# SCH_UWB_2026-08-28.net
KiCad netlist of a schematic drawn in EasyEDA
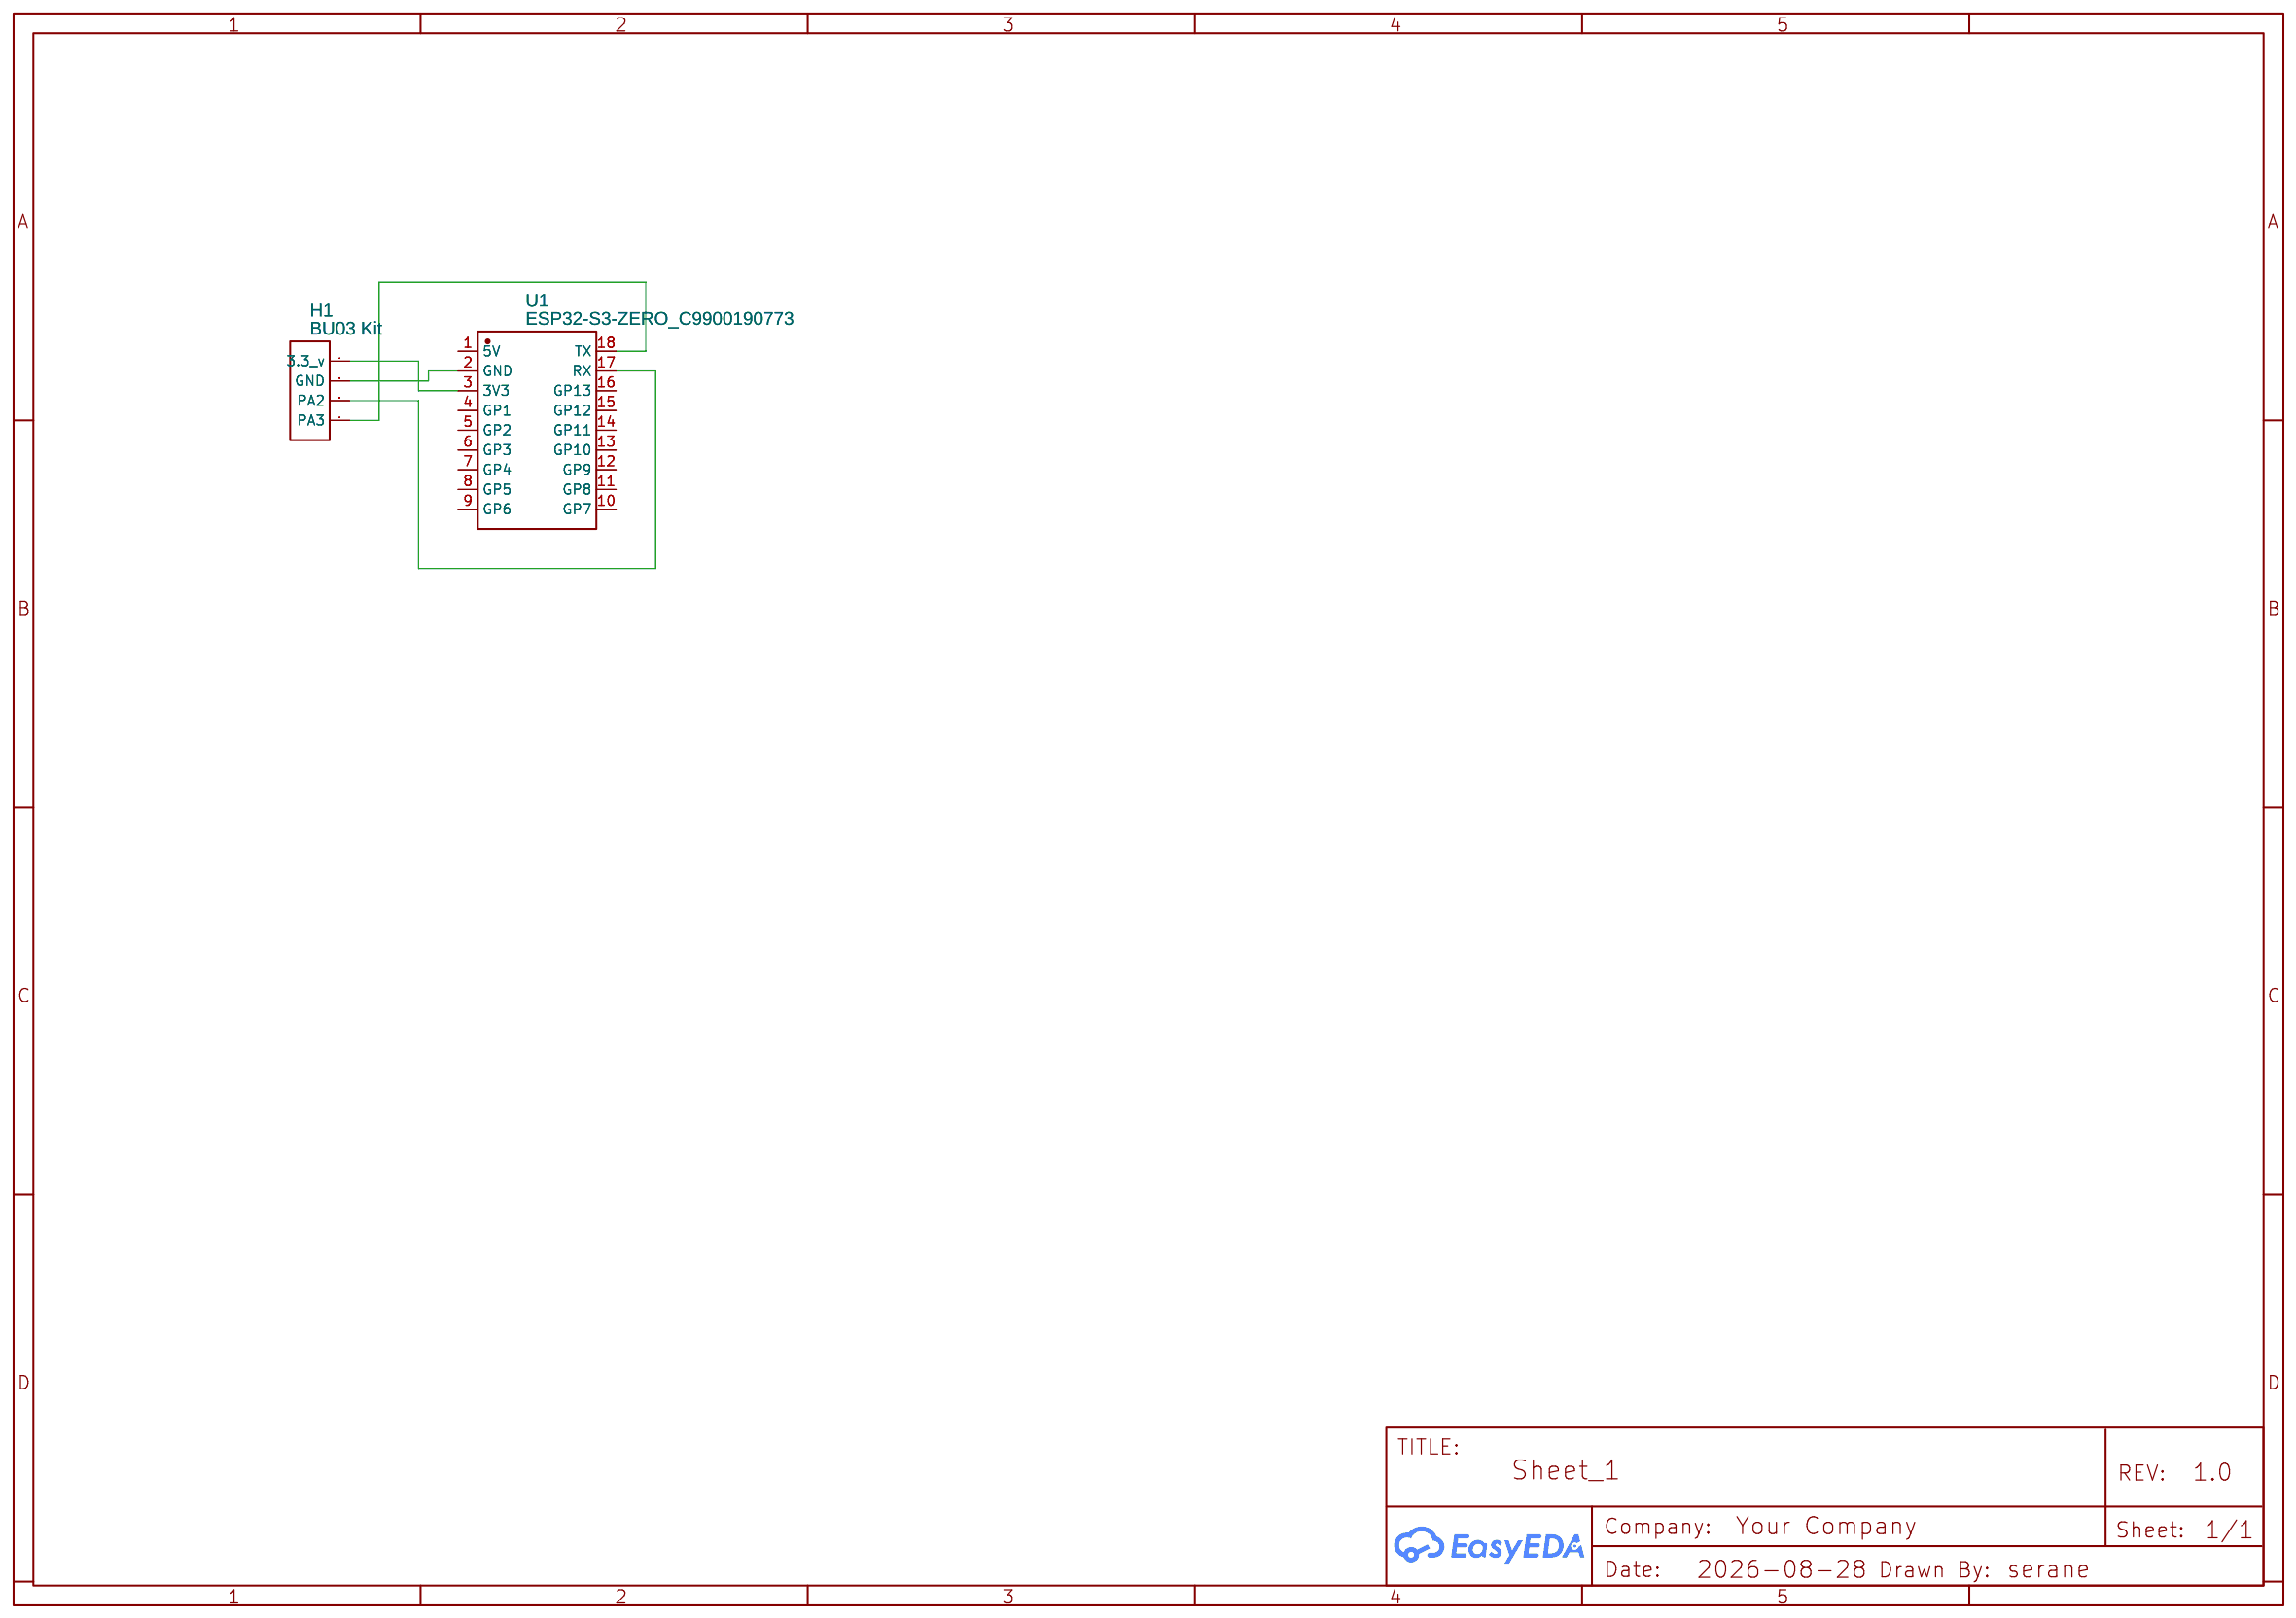
[diagram p0: schematic sheet]

(export (version "E")
  (design (tool "Eeschema 10.0.6"))
  (components
    (comp (ref "H1") (value "BU03 Kit") (libsource (lib "") (part "HDR-F-2.54_1x4")))
    (comp (ref "U1")
      (value "ESP32-S3-ZERO_C9900190773")
      (fields (field (name "Manufacturer Part") "ESP32-S3-Zero"))
      (libsource (lib "") (part "ESP32-S3-ZERO_C9900190773"))
    )
  )
  (nets
    (net (code "1") (name "Net-(H1-3.3_v)") (class "Default")
      (node (ref "H1") (pin "4") (pinfunction "3.3_v_4") (pintype "unspecified"))
      (node (ref "U1") (pin "3") (pinfunction "3V3_3") (pintype "unspecified"))
    )
    (net (code "2") (name "Net-(H1-GND)") (class "Default")
      (node (ref "H1") (pin "3") (pinfunction "GND_3") (pintype "unspecified"))
      (node (ref "U1") (pin "2") (pinfunction "GND_2") (pintype "unspecified"))
    )
    (net (code "3") (name "Net-(H1-PA2)") (class "Default")
      (node (ref "H1") (pin "2") (pinfunction "PA2_2") (pintype "unspecified"))
      (node (ref "U1") (pin "17") (pinfunction "RX_17") (pintype "unspecified"))
    )
    (net (code "4") (name "Net-(H1-PA3)") (class "Default")
      (node (ref "H1") (pin "1") (pinfunction "PA3_1") (pintype "unspecified"))
      (node (ref "U1") (pin "18") (pinfunction "TX_18") (pintype "unspecified"))
    )
    (net (code "5") (name "unconnected-(U1-5V-Pad1)") (class "Default")
      (node (ref "U1") (pin "1") (pinfunction "5V_1") (pintype "unspecified"))
    )
    (net (code "6") (name "unconnected-(U1-GP1-Pad4)") (class "Default")
      (node (ref "U1") (pin "4") (pinfunction "GP1_4") (pintype "unspecified"))
    )
    (net (code "7") (name "unconnected-(U1-GP2-Pad5)") (class "Default")
      (node (ref "U1") (pin "5") (pinfunction "GP2_5") (pintype "unspecified"))
    )
    (net (code "8") (name "unconnected-(U1-GP3-Pad6)") (class "Default")
      (node (ref "U1") (pin "6") (pinfunction "GP3_6") (pintype "unspecified"))
    )
    (net (code "9") (name "unconnected-(U1-GP4-Pad7)") (class "Default")
      (node (ref "U1") (pin "7") (pinfunction "GP4_7") (pintype "unspecified"))
    )
    (net (code "10") (name "unconnected-(U1-GP5-Pad8)") (class "Default")
      (node (ref "U1") (pin "8") (pinfunction "GP5_8") (pintype "unspecified"))
    )
    (net (code "11") (name "unconnected-(U1-GP6-Pad9)") (class "Default")
      (node (ref "U1") (pin "9") (pinfunction "GP6_9") (pintype "unspecified"))
    )
    (net (code "12") (name "unconnected-(U1-GP7-Pad10)") (class "Default")
      (node (ref "U1") (pin "10") (pinfunction "GP7_10") (pintype "unspecified"))
    )
    (net (code "13") (name "unconnected-(U1-GP8-Pad11)") (class "Default")
      (node (ref "U1") (pin "11") (pinfunction "GP8_11") (pintype "unspecified"))
    )
    (net (code "14") (name "unconnected-(U1-GP9-Pad12)") (class "Default")
      (node (ref "U1") (pin "12") (pinfunction "GP9_12") (pintype "unspecified"))
    )
    (net (code "15") (name "unconnected-(U1-GP10-Pad13)") (class "Default")
      (node (ref "U1") (pin "13") (pinfunction "GP10_13") (pintype "unspecified"))
    )
    (net (code "16") (name "unconnected-(U1-GP11-Pad14)") (class "Default")
      (node (ref "U1") (pin "14") (pinfunction "GP11_14") (pintype "unspecified"))
    )
    (net (code "17") (name "unconnected-(U1-GP12-Pad15)") (class "Default")
      (node (ref "U1") (pin "15") (pinfunction "GP12_15") (pintype "unspecified"))
    )
    (net (code "18") (name "unconnected-(U1-GP13-Pad16)") (class "Default")
      (node (ref "U1") (pin "16") (pinfunction "GP13_16") (pintype "unspecified"))
    )
  )
)
